# RX-FM-Radio-Circuit-Mirrored.net
KiCad netlist of a schematic drawn in EAGLE
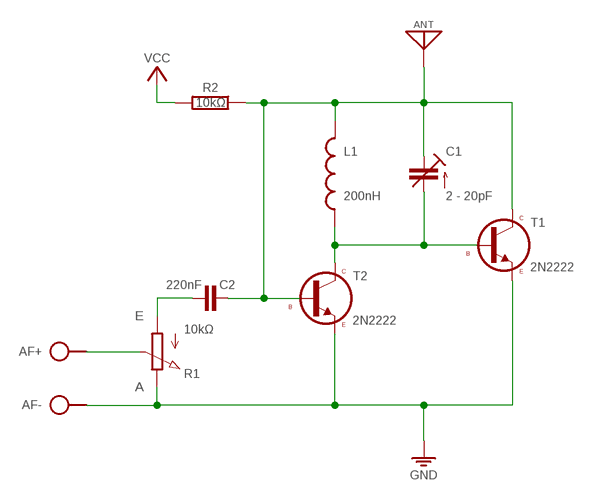
[diagram p0: schematic, sheet 1]

(export (version "E")
  (design (tool "Eeschema 10.0.6"))
  (components
    (comp (ref "AF")
      (value "SPAD+-+-")
      (footprint "eagle-import:SPAD+-")
      (libsource (lib "eagle-import") (part "SPAD+-+-"))
    )
    (comp (ref "ANT")
      (value "ANT")
      (footprint "eagle-import:SPAD")
      (libsource (lib "eagle-import") (part "ANT"))
    )
    (comp (ref "BAT")
      (value "VCC_GNDL")
      (footprint "eagle-import:SPAD-+")
      (libsource (lib "eagle-import") (part "VCC_GNDL"))
    )
    (comp (ref "C1")
      (value "2 - 20pF")
      (footprint "eagle-import:TRIM-2222-808")
      (libsource (lib "eagle-import") (part "C-TR-PH201272222-808-2PIN"))
    )
    (comp (ref "C2")
      (value "220nF")
      (footprint "eagle-import:C050-020X044")
      (libsource (lib "eagle-import") (part "C-H050-020X044"))
    )
    (comp (ref "L1")
      (value "200nH")
      (footprint "eagle-import:L-04_7-V")
      (libsource (lib "eagle-import") (part "L04/7-V"))
    )
    (comp (ref "R1")
      (value "10kΩ")
      (footprint "eagle-import:CONN-3P")
      (libsource (lib "eagle-import") (part "POT-3P"))
    )
    (comp (ref "R2")
      (value "10kΩ")
      (footprint "eagle-import:0204_10")
      (libsource (lib "eagle-import") (part "R-H0204/10"))
    )
    (comp (ref "T1")
      (value "2N2222")
      (footprint "eagle-import:TO92-EBC")
      (libsource (lib "eagle-import") (part "2N2222"))
    )
    (comp (ref "T2")
      (value "2N2222")
      (footprint "eagle-import:TO92-EBC")
      (libsource (lib "eagle-import") (part "2N2222"))
    )
  )
  (nets
    (net (code "1") (name "Net-(AFA-P$1)") (class "Default")
      (node (ref "AF") (pin "2") (pinfunction "P$1_2") (pintype "passive"))
      (node (ref "R1") (pin "2") (pinfunction "S_2") (pintype "passive"))
    )
    (net (code "2") (name "Net-(AFB-P$1)") (class "Default")
      (node (ref "AF") (pin "1") (pinfunction "P$1_1") (pintype "passive"))
      (node (ref "BAT") (pin "1") (pinfunction "GND_1") (pintype "power_in"))
      (node (ref "R1") (pin "3") (pinfunction "E_3") (pintype "passive"))
      (node (ref "T1") (pin "E") (pinfunction "E_E") (pintype "passive"))
      (node (ref "T2") (pin "E") (pinfunction "E_E") (pintype "passive"))
    )
    (net (code "3") (name "Net-(BATA-VCC)") (class "Default")
      (node (ref "BAT") (pin "2") (pinfunction "VCC_2") (pintype "power_in"))
      (node (ref "R2") (pin "2") (pinfunction "2_2") (pintype "passive"))
    )
    (net (code "4") (name "Net-(C1-A)") (class "Default")
      (node (ref "C1") (pin "2") (pinfunction "A_2") (pintype "passive"))
      (node (ref "L1") (pin "2") (pinfunction "2_2") (pintype "passive"))
      (node (ref "T1") (pin "B") (pinfunction "B_B") (pintype "passive"))
      (node (ref "T2") (pin "C") (pinfunction "C_C") (pintype "passive"))
    )
    (net (code "5") (name "Net-(C1-E)") (class "Default")
      (node (ref "ANT") (pin "1") (pinfunction "1_1") (pintype "output"))
      (node (ref "C1") (pin "1") (pinfunction "E_1") (pintype "passive"))
      (node (ref "C2") (pin "1") (pinfunction "1_1") (pintype "passive"))
      (node (ref "L1") (pin "1") (pinfunction "1_1") (pintype "passive"))
      (node (ref "R2") (pin "1") (pinfunction "1_1") (pintype "passive"))
      (node (ref "T1") (pin "C") (pinfunction "C_C") (pintype "passive"))
      (node (ref "T2") (pin "B") (pinfunction "B_B") (pintype "passive"))
    )
    (net (code "6") (name "Net-(R1-A)") (class "Default")
      (node (ref "C2") (pin "2") (pinfunction "2_2") (pintype "passive"))
      (node (ref "R1") (pin "1") (pinfunction "A_1") (pintype "passive"))
    )
  )
)
